# tick-display-mk-2_3-mini.net
KiCad netlist of a schematic drawn in EAGLE
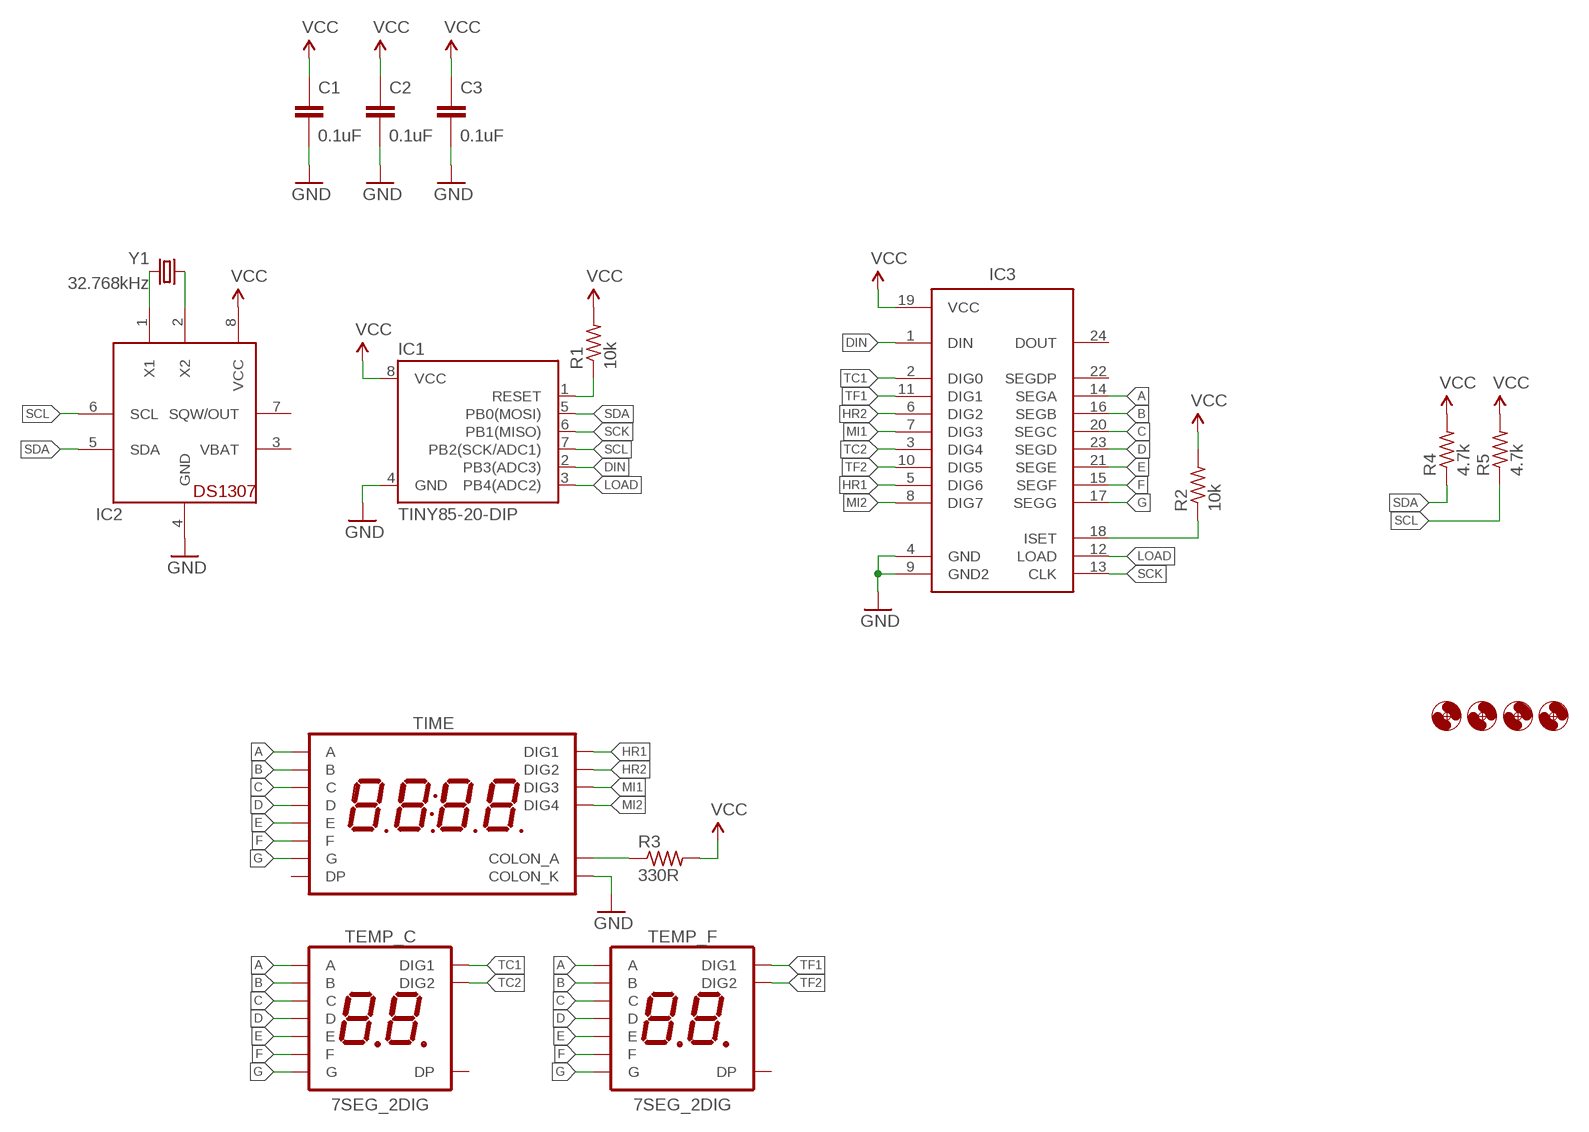
[diagram p0: schematic, sheet 1]

(export (version "E")
  (design (tool "Eeschema 10.0.6"))
  (components
    (comp (ref "C1")
      (value "0.1uF")
      (footprint "eagle-import:C025-024X044")
      (libsource (lib "eagle-import") (part "CAPACITOR-CERAMIC025-024X044"))
    )
    (comp (ref "C2")
      (value "0.1uF")
      (footprint "eagle-import:C025-024X044")
      (libsource (lib "eagle-import") (part "CAPACITOR-CERAMIC025-024X044"))
    )
    (comp (ref "C3")
      (value "0.1uF")
      (footprint "eagle-import:C025-024X044")
      (libsource (lib "eagle-import") (part "CAPACITOR-CERAMIC025-024X044"))
    )
    (comp (ref "H1")
      (value "HOLE#2")
      (footprint "eagle-import:HOLE-#2")
      (libsource (lib "eagle-import") (part "HOLE#2"))
    )
    (comp (ref "H2")
      (value "HOLE#2")
      (footprint "eagle-import:HOLE-#2")
      (libsource (lib "eagle-import") (part "HOLE#2"))
    )
    (comp (ref "H3")
      (value "HOLE#2")
      (footprint "eagle-import:HOLE-#2")
      (libsource (lib "eagle-import") (part "HOLE#2"))
    )
    (comp (ref "H4")
      (value "HOLE#2")
      (footprint "eagle-import:HOLE-#2")
      (libsource (lib "eagle-import") (part "HOLE#2"))
    )
    (comp (ref "IC1")
      (value "TINY85-20-DIP")
      (footprint "eagle-import:DIP08")
      (libsource (lib "eagle-import") (part "ATTINY45TINY85-20-DIP"))
    )
    (comp (ref "IC2")
      (value "DS1307")
      (footprint "eagle-import:DIL08")
      (libsource (lib "eagle-import") (part "DS1307"))
    )
    (comp (ref "IC3")
      (value "MAX7219DIP")
      (footprint "eagle-import:DIL24")
      (libsource (lib "eagle-import") (part "MAX7219DIP"))
    )
    (comp (ref "R1")
      (value "10k")
      (footprint "eagle-import:RESISTOR-AXIAL-PTH-5.08MM")
      (libsource (lib "eagle-import") (part "RESISTORPTH-AXIAL-5.08MM"))
    )
    (comp (ref "R2")
      (value "10k")
      (footprint "eagle-import:RESISTOR-AXIAL-PTH-5.08MM")
      (libsource (lib "eagle-import") (part "RESISTORPTH-AXIAL-5.08MM"))
    )
    (comp (ref "R3")
      (value "330R")
      (footprint "eagle-import:RESISTOR-AXIAL-PTH-5.08MM")
      (libsource (lib "eagle-import") (part "RESISTORPTH-AXIAL-5.08MM"))
    )
    (comp (ref "R4")
      (value "4.7k")
      (footprint "eagle-import:RESISTOR-AXIAL-PTH-5.08MM")
      (libsource (lib "eagle-import") (part "RESISTORPTH-AXIAL-5.08MM"))
    )
    (comp (ref "R5")
      (value "4.7k")
      (footprint "eagle-import:RESISTOR-AXIAL-PTH-5.08MM")
      (libsource (lib "eagle-import") (part "RESISTORPTH-AXIAL-5.08MM"))
    )
    (comp (ref "TEMP_C")
      (value "7SEG_2DIG")
      (footprint "eagle-import:7SEG_2DIG_14MM")
      (libsource (lib "eagle-import") (part "7SEG_2DIG"))
    )
    (comp (ref "TEMP_F")
      (value "7SEG_2DIG")
      (footprint "eagle-import:7SEG_2DIG_14MM")
      (libsource (lib "eagle-import") (part "7SEG_2DIG"))
    )
    (comp (ref "TIME")
      (value "7SED_4DIGIT_14MM14.2MM-CC")
      (footprint "eagle-import:7SEG_4DIG")
      (libsource (lib "eagle-import") (part "7SED_4DIGIT_14MM14.2MM-CC"))
    )
    (comp (ref "Y1")
      (value "32.768kHz")
      (footprint "eagle-import:TC26H")
      (libsource (lib "eagle-import") (part "CRYSTALTC26H"))
    )
  )
  (nets
    (net (code "1") (name "/VBAT") (class "Default")
      (node (ref "IC2") (pin "3") (pinfunction "VBAT_3") (pintype "power_in"))
    )
    (net (code "2") (name "A") (class "Default")
      (node (ref "IC3") (pin "14") (pinfunction "SEGA_14") (pintype "bidirectional"))
      (node (ref "TEMP_C") (pin "4") (pinfunction "A_4") (pintype "passive"))
      (node (ref "TEMP_F") (pin "4") (pinfunction "A_4") (pintype "passive"))
      (node (ref "TIME") (pin "P$13") (pinfunction "A_P$13") (pintype "passive"))
    )
    (net (code "3") (name "B") (class "Default")
      (node (ref "IC3") (pin "16") (pinfunction "SEGB_16") (pintype "bidirectional"))
      (node (ref "TEMP_C") (pin "3") (pinfunction "B_3") (pintype "passive"))
      (node (ref "TEMP_F") (pin "3") (pinfunction "B_3") (pintype "passive"))
      (node (ref "TIME") (pin "P$9") (pinfunction "B_P$9") (pintype "passive"))
    )
    (net (code "4") (name "C") (class "Default")
      (node (ref "IC3") (pin "20") (pinfunction "SEGC_20") (pintype "bidirectional"))
      (node (ref "TEMP_C") (pin "9") (pinfunction "C_9") (pintype "passive"))
      (node (ref "TEMP_F") (pin "9") (pinfunction "C_9") (pintype "passive"))
      (node (ref "TIME") (pin "P$4") (pinfunction "C_P$4") (pintype "passive"))
    )
    (net (code "5") (name "D") (class "Default")
      (node (ref "IC3") (pin "23") (pinfunction "SEGD_23") (pintype "bidirectional"))
      (node (ref "TEMP_C") (pin "8") (pinfunction "D_8") (pintype "passive"))
      (node (ref "TEMP_F") (pin "8") (pinfunction "D_8") (pintype "passive"))
      (node (ref "TIME") (pin "P$2") (pinfunction "D_P$2") (pintype "passive"))
    )
    (net (code "6") (name "DIN") (class "Default")
      (node (ref "IC1") (pin "2") (pinfunction "PB3(ADC3)_2") (pintype "bidirectional"))
      (node (ref "IC3") (pin "1") (pinfunction "DIN_1") (pintype "bidirectional"))
    )
    (net (code "7") (name "E") (class "Default")
      (node (ref "IC3") (pin "21") (pinfunction "SEGE_21") (pintype "bidirectional"))
      (node (ref "TEMP_C") (pin "6") (pinfunction "E_6") (pintype "passive"))
      (node (ref "TEMP_F") (pin "6") (pinfunction "E_6") (pintype "passive"))
      (node (ref "TIME") (pin "P$1") (pinfunction "E_P$1") (pintype "passive"))
    )
    (net (code "8") (name "F") (class "Default")
      (node (ref "IC3") (pin "15") (pinfunction "SEGF_15") (pintype "bidirectional"))
      (node (ref "TEMP_C") (pin "7") (pinfunction "F_7") (pintype "passive"))
      (node (ref "TEMP_F") (pin "7") (pinfunction "F_7") (pintype "passive"))
      (node (ref "TIME") (pin "P$12") (pinfunction "F_P$12") (pintype "passive"))
    )
    (net (code "9") (name "G") (class "Default")
      (node (ref "IC3") (pin "17") (pinfunction "SEGG_17") (pintype "bidirectional"))
      (node (ref "TEMP_C") (pin "1") (pinfunction "G_1") (pintype "passive"))
      (node (ref "TEMP_F") (pin "1") (pinfunction "G_1") (pintype "passive"))
      (node (ref "TIME") (pin "P$5") (pinfunction "G_P$5") (pintype "passive"))
    )
    (net (code "10") (name "GND") (class "Default")
      (node (ref "C1") (pin "2") (pinfunction "2_2") (pintype "passive"))
      (node (ref "C2") (pin "2") (pinfunction "2_2") (pintype "passive"))
      (node (ref "C3") (pin "2") (pinfunction "2_2") (pintype "passive"))
      (node (ref "IC1") (pin "4") (pinfunction "GND_4") (pintype "bidirectional"))
      (node (ref "IC2") (pin "4") (pinfunction "GND_4") (pintype "power_in"))
      (node (ref "IC3") (pin "4") (pinfunction "GND_4") (pintype "bidirectional"))
      (node (ref "IC3") (pin "9") (pinfunction "GND2_9") (pintype "bidirectional"))
      (node (ref "TIME") (pin "P$7") (pinfunction "COLON_K_P$7") (pintype "passive"))
    )
    (net (code "11") (name "HR1") (class "Default")
      (node (ref "IC3") (pin "5") (pinfunction "DIG6_5") (pintype "bidirectional"))
      (node (ref "TIME") (pin "P$14") (pinfunction "DIG1_P$14") (pintype "passive"))
    )
    (net (code "12") (name "HR2") (class "Default")
      (node (ref "IC3") (pin "6") (pinfunction "DIG2_6") (pintype "bidirectional"))
      (node (ref "TIME") (pin "P$11") (pinfunction "DIG2_P$11") (pintype "passive"))
    )
    (net (code "13") (name "LOAD") (class "Default")
      (node (ref "IC1") (pin "3") (pinfunction "PB4(ADC2)_3") (pintype "bidirectional"))
      (node (ref "IC3") (pin "12") (pinfunction "LOAD_12") (pintype "bidirectional"))
    )
    (net (code "14") (name "MI1") (class "Default")
      (node (ref "IC3") (pin "7") (pinfunction "DIG3_7") (pintype "bidirectional"))
      (node (ref "TIME") (pin "P$10") (pinfunction "DIG3_P$10") (pintype "passive"))
    )
    (net (code "15") (name "MI2") (class "Default")
      (node (ref "IC3") (pin "8") (pinfunction "DIG7_8") (pintype "bidirectional"))
      (node (ref "TIME") (pin "P$6") (pinfunction "DIG4_P$6") (pintype "passive"))
    )
    (net (code "16") (name "Net-(IC1-RESET)") (class "Default")
      (node (ref "IC1") (pin "1") (pinfunction "RESET_1") (pintype "bidirectional"))
      (node (ref "R1") (pin "P$1") (pinfunction "1_P$1") (pintype "passive"))
    )
    (net (code "17") (name "Net-(IC2-X1)") (class "Default")
      (node (ref "IC2") (pin "1") (pinfunction "X1_1") (pintype "passive"))
      (node (ref "Y1") (pin "2") (pinfunction "2_2") (pintype "passive"))
    )
    (net (code "18") (name "Net-(IC2-X2)") (class "Default")
      (node (ref "IC2") (pin "2") (pinfunction "X2_2") (pintype "passive"))
      (node (ref "Y1") (pin "1") (pinfunction "1_1") (pintype "passive"))
    )
    (net (code "19") (name "Net-(IC3-ISET)") (class "Default")
      (node (ref "IC3") (pin "18") (pinfunction "ISET_18") (pintype "bidirectional"))
      (node (ref "R2") (pin "P$1") (pinfunction "1_P$1") (pintype "passive"))
    )
    (net (code "20") (name "Net-(R3-1)") (class "Default")
      (node (ref "R3") (pin "P$1") (pinfunction "1_P$1") (pintype "passive"))
      (node (ref "TIME") (pin "P$8") (pinfunction "COLON_A_P$8") (pintype "passive"))
    )
    (net (code "21") (name "SCK") (class "Default")
      (node (ref "IC1") (pin "6") (pinfunction "PB1(MISO)_6") (pintype "bidirectional"))
      (node (ref "IC3") (pin "13") (pinfunction "CLK_13") (pintype "bidirectional"))
    )
    (net (code "22") (name "SCL") (class "Default")
      (node (ref "IC1") (pin "7") (pinfunction "PB2(SCK/ADC1)_7") (pintype "bidirectional"))
      (node (ref "IC2") (pin "6") (pinfunction "SCL_6") (pintype "bidirectional"))
      (node (ref "R5") (pin "P$1") (pinfunction "1_P$1") (pintype "passive"))
    )
    (net (code "23") (name "SDA") (class "Default")
      (node (ref "IC1") (pin "5") (pinfunction "PB0(MOSI)_5") (pintype "bidirectional"))
      (node (ref "IC2") (pin "5") (pinfunction "SDA_5") (pintype "bidirectional"))
      (node (ref "R4") (pin "P$1") (pinfunction "1_P$1") (pintype "passive"))
    )
    (net (code "24") (name "TC1") (class "Default")
      (node (ref "IC3") (pin "2") (pinfunction "DIG0_2") (pintype "bidirectional"))
      (node (ref "TEMP_C") (pin "5") (pinfunction "DIG1_5") (pintype "passive"))
    )
    (net (code "25") (name "TC2") (class "Default")
      (node (ref "IC3") (pin "3") (pinfunction "DIG4_3") (pintype "bidirectional"))
      (node (ref "TEMP_C") (pin "10") (pinfunction "DIG2_10") (pintype "passive"))
    )
    (net (code "26") (name "TF1") (class "Default")
      (node (ref "IC3") (pin "11") (pinfunction "DIG1_11") (pintype "bidirectional"))
      (node (ref "TEMP_F") (pin "5") (pinfunction "DIG1_5") (pintype "passive"))
    )
    (net (code "27") (name "TF2") (class "Default")
      (node (ref "IC3") (pin "10") (pinfunction "DIG5_10") (pintype "bidirectional"))
      (node (ref "TEMP_F") (pin "10") (pinfunction "DIG2_10") (pintype "passive"))
    )
    (net (code "28") (name "VCC") (class "Default")
      (node (ref "C1") (pin "1") (pinfunction "1_1") (pintype "passive"))
      (node (ref "C2") (pin "1") (pinfunction "1_1") (pintype "passive"))
      (node (ref "C3") (pin "1") (pinfunction "1_1") (pintype "passive"))
      (node (ref "IC1") (pin "8") (pinfunction "VCC_8") (pintype "bidirectional"))
      (node (ref "IC2") (pin "8") (pinfunction "VCC_8") (pintype "power_in"))
      (node (ref "IC3") (pin "19") (pinfunction "VCC_19") (pintype "bidirectional"))
      (node (ref "R1") (pin "P$2") (pinfunction "2_P$2") (pintype "passive"))
      (node (ref "R2") (pin "P$2") (pinfunction "2_P$2") (pintype "passive"))
      (node (ref "R3") (pin "P$2") (pinfunction "2_P$2") (pintype "passive"))
      (node (ref "R4") (pin "P$2") (pinfunction "2_P$2") (pintype "passive"))
      (node (ref "R5") (pin "P$2") (pinfunction "2_P$2") (pintype "passive"))
    )
    (net (code "29") (name "unconnected-(IC2-SQW{slash}OUT-Pad7)") (class "Default")
      (node (ref "IC2") (pin "7") (pinfunction "SQW/OUT_7") (pintype "bidirectional"))
    )
    (net (code "30") (name "unconnected-(IC3-DOUT-Pad24)") (class "Default")
      (node (ref "IC3") (pin "24") (pinfunction "DOUT_24") (pintype "bidirectional"))
    )
    (net (code "31") (name "unconnected-(IC3-SEGDP-Pad22)") (class "Default")
      (node (ref "IC3") (pin "22") (pinfunction "SEGDP_22") (pintype "bidirectional"))
    )
    (net (code "32") (name "unconnected-(TEMP_C-DP-Pad2)") (class "Default")
      (node (ref "TEMP_C") (pin "2") (pinfunction "DP_2") (pintype "passive"))
    )
    (net (code "33") (name "unconnected-(TEMP_F-DP-Pad2)") (class "Default")
      (node (ref "TEMP_F") (pin "2") (pinfunction "DP_2") (pintype "passive"))
    )
    (net (code "34") (name "unconnected-(TIME-DP-PadP$3)") (class "Default")
      (node (ref "TIME") (pin "P$3") (pinfunction "DP_P$3") (pintype "passive"))
    )
  )
)
